# OSP_Carrier_V8_Power.net
KiCad netlist of a schematic drawn in Altium Designer
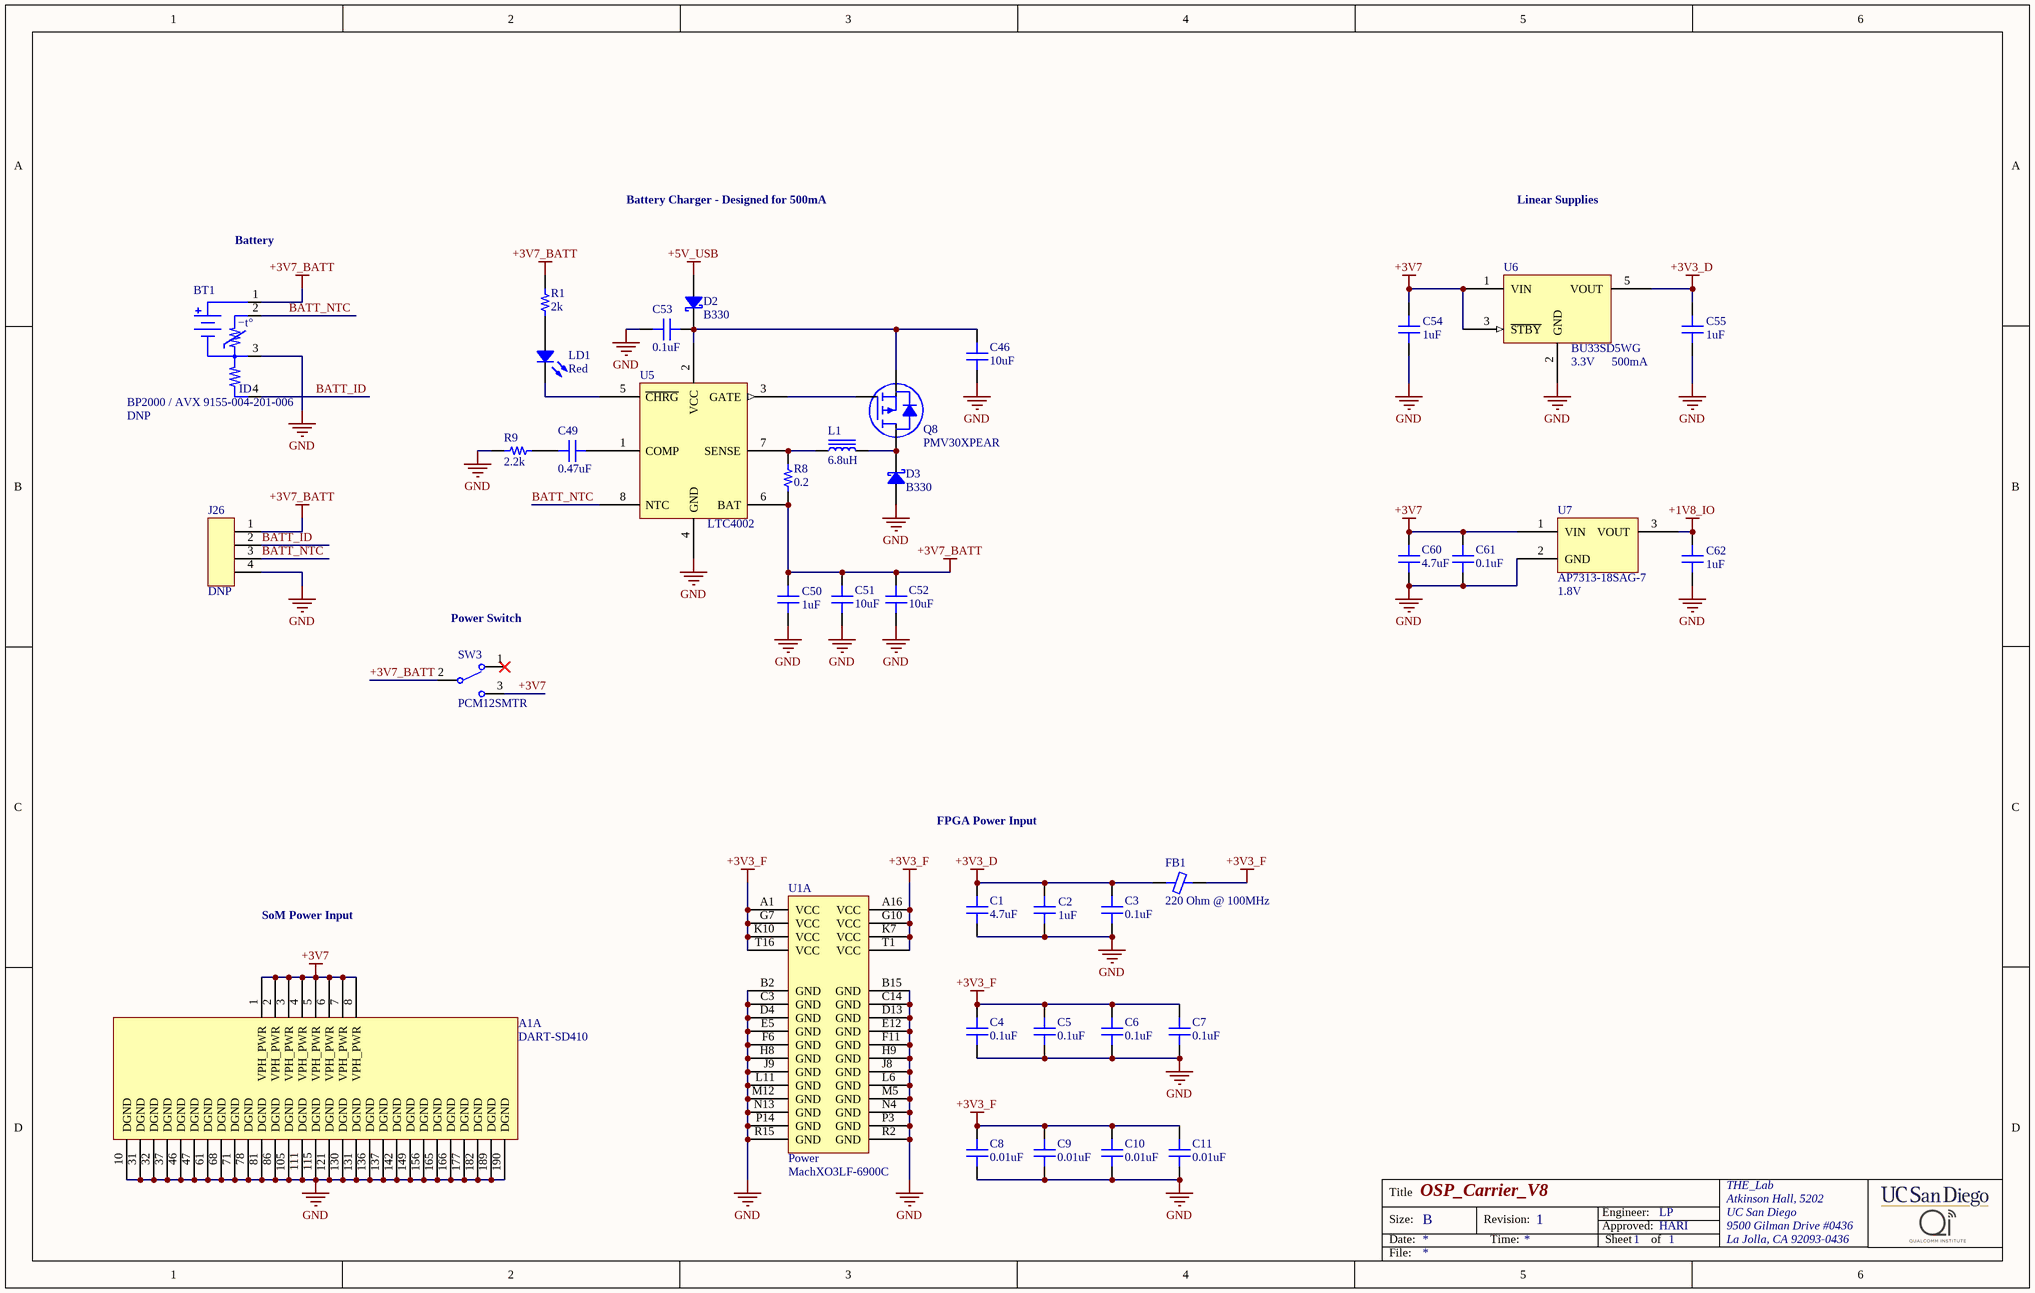
[diagram p0: OSP_Carrier_V8_Power.SchDoc]

(export (version "E")
  (design (tool "Eeschema 10.0.6"))
  (components
    (comp (ref "A1")
      (value "DART-SD410")
      (footprint "DART-SD410")
      (description "Variscite DART-SD410 System on Module")
      (libsource (lib "DART-SD410") (part "DART-SD410"))
    )
    (comp (ref "BT1")
      (value "BP2000 / AVX 9155-004-201-006")
      (footprint "SAMSUNG_BP2000")
      (description "Samsung BP2000 2000mAh battery for Galaxy Camera 2, connector AVX 9155-004-201-006")
      (fields (field (name "DNP") "DNP"))
      (libsource (lib "OSP_Symbols") (part "SAMSUNG_BP2000"))
    )
    (comp (ref "C1")
      (value "4.7uF")
      (footprint "CAP 0402/1005")
      (description "CAP CER 4.7UF 10V X5R 0402")
      (fields
        (field (name "PART NUMBER") "C1005X5R1A475K050BC")
        (field (name "MANUFACTURER") "TDK Corporation")
      )
      (libsource (lib "Celestial Library Database") (part "Capacitor"))
    )
    (comp (ref "C2")
      (value "1uF")
      (footprint "CAP 0402/1005")
      (description "CAP CER 1UF 10V X5R 0402")
      (fields
        (field (name "PART NUMBER") "GRM155R61A105KE15D")
        (field (name "MANUFACTURER") "Murata Electronics North America")
      )
      (libsource (lib "Celestial Library Database") (part "Capacitor"))
    )
    (comp (ref "C3")
      (value "0.1uF")
      (footprint "CAP 0402/1005")
      (description "CAP CER 0.1UF 50V X7R 0402")
      (fields
        (field (name "PART NUMBER") "C1005X7R1H104K050BB")
        (field (name "MANUFACTURER") "TDK Corporation")
      )
      (libsource (lib "Celestial Library Database") (part "Capacitor"))
    )
    (comp (ref "C4")
      (value "0.1uF")
      (footprint "CAP 0402/1005")
      (description "CAP CER 0.1UF 50V X7R 0402")
      (fields
        (field (name "PART NUMBER") "C1005X7R1H104K050BB")
        (field (name "MANUFACTURER") "TDK Corporation")
      )
      (libsource (lib "Celestial Library Database") (part "Capacitor"))
    )
    (comp (ref "C5")
      (value "0.1uF")
      (footprint "CAP 0402/1005")
      (description "CAP CER 0.1UF 50V X7R 0402")
      (fields
        (field (name "PART NUMBER") "C1005X7R1H104K050BB")
        (field (name "MANUFACTURER") "TDK Corporation")
      )
      (libsource (lib "Celestial Library Database") (part "Capacitor"))
    )
    (comp (ref "C6")
      (value "0.1uF")
      (footprint "CAP 0402/1005")
      (description "CAP CER 0.1UF 50V X7R 0402")
      (fields
        (field (name "PART NUMBER") "C1005X7R1H104K050BB")
        (field (name "MANUFACTURER") "TDK Corporation")
      )
      (libsource (lib "Celestial Library Database") (part "Capacitor"))
    )
    (comp (ref "C7")
      (value "0.1uF")
      (footprint "CAP 0402/1005")
      (description "CAP CER 0.1UF 50V X7R 0402")
      (fields
        (field (name "PART NUMBER") "C1005X7R1H104K050BB")
        (field (name "MANUFACTURER") "TDK Corporation")
      )
      (libsource (lib "Celestial Library Database") (part "Capacitor"))
    )
    (comp (ref "C8")
      (value "0.01uF")
      (footprint "CAP 0402/1005")
      (description "CAP CER 10000PF 25V X7R 0402")
      (fields (field (name "PART NUMBER") "CC0402KRX7R8BB103") (field (name "MANUFACTURER") "Yageo"))
      (libsource (lib "Celestial Library Database") (part "Capacitor"))
    )
    (comp (ref "C9")
      (value "0.01uF")
      (footprint "CAP 0402/1005")
      (description "CAP CER 10000PF 25V X7R 0402")
      (fields (field (name "PART NUMBER") "CC0402KRX7R8BB103") (field (name "MANUFACTURER") "Yageo"))
      (libsource (lib "Celestial Library Database") (part "Capacitor"))
    )
    (comp (ref "C10")
      (value "0.01uF")
      (footprint "CAP 0402/1005")
      (description "CAP CER 10000PF 25V X7R 0402")
      (fields (field (name "PART NUMBER") "CC0402KRX7R8BB103") (field (name "MANUFACTURER") "Yageo"))
      (libsource (lib "Celestial Library Database") (part "Capacitor"))
    )
    (comp (ref "C11")
      (value "0.01uF")
      (footprint "CAP 0402/1005")
      (description "CAP CER 10000PF 25V X7R 0402")
      (fields (field (name "PART NUMBER") "CC0402KRX7R8BB103") (field (name "MANUFACTURER") "Yageo"))
      (libsource (lib "Celestial Library Database") (part "Capacitor"))
    )
    (comp (ref "C46")
      (value "10uF")
      (footprint "CAP 1206/3216")
      (description "CAP CER 10UF 25V X7R 1206")
      (fields (field (name "PART NUMBER") "C1206C106M3RACTU") (field (name "MANUFACTURER") "Kemet"))
      (libsource (lib "Celestial Library Database") (part "Capacitor"))
    )
    (comp (ref "C49")
      (value "0.47uF")
      (footprint "CAP 0402/1005")
      (description "CAP CER 0.47UF 10V X5R 0402")
      (fields
        (field (name "PART NUMBER") "GRM155R61A474KE15D")
        (field (name "MANUFACTURER") "Murata Electronics North America")
      )
      (libsource (lib "Celestial Library Database") (part "Capacitor"))
    )
    (comp (ref "C50")
      (value "1uF")
      (footprint "CAP 0402/1005")
      (description "CAP CER 1UF 10V X5R 0402")
      (fields
        (field (name "PART NUMBER") "GRM155R61A105KE15D")
        (field (name "MANUFACTURER") "Murata Electronics North America")
      )
      (libsource (lib "Celestial Library Database") (part "Capacitor"))
    )
    (comp (ref "C51")
      (value "10uF")
      (footprint "CAP 1206/3216")
      (description "CAP CER 10UF 25V X7R 1206")
      (fields (field (name "PART NUMBER") "C1206C106M3RACTU") (field (name "MANUFACTURER") "Kemet"))
      (libsource (lib "Celestial Library Database") (part "Capacitor"))
    )
    (comp (ref "C52")
      (value "10uF")
      (footprint "CAP 1206/3216")
      (description "CAP CER 10UF 25V X7R 1206")
      (fields (field (name "PART NUMBER") "C1206C106M3RACTU") (field (name "MANUFACTURER") "Kemet"))
      (libsource (lib "Celestial Library Database") (part "Capacitor"))
    )
    (comp (ref "C53")
      (value "0.1uF")
      (footprint "CAP 0402/1005")
      (description "CAP CER 0.1UF 50V X7R 0402")
      (fields
        (field (name "PART NUMBER") "C1005X7R1H104K050BB")
        (field (name "MANUFACTURER") "TDK Corporation")
      )
      (libsource (lib "Celestial Library Database") (part "Capacitor"))
    )
    (comp (ref "C54")
      (value "1uF")
      (footprint "CAP 0402/1005")
      (description "CAP CER 1UF 10V X5R 0402")
      (fields
        (field (name "PART NUMBER") "GRM155R61A105KE15D")
        (field (name "MANUFACTURER") "Murata Electronics North America")
      )
      (libsource (lib "Celestial Library Database") (part "Capacitor"))
    )
    (comp (ref "C55")
      (value "1uF")
      (footprint "CAP 0402/1005")
      (description "CAP CER 1UF 10V X5R 0402")
      (fields
        (field (name "PART NUMBER") "GRM155R61A105KE15D")
        (field (name "MANUFACTURER") "Murata Electronics North America")
      )
      (libsource (lib "Celestial Library Database") (part "Capacitor"))
    )
    (comp (ref "C60")
      (value "4.7uF")
      (footprint "CAP 0402/1005")
      (description "CAP CER 4.7UF 10V X5R 0402")
      (fields
        (field (name "PART NUMBER") "C1005X5R1A475K050BC")
        (field (name "MANUFACTURER") "TDK Corporation")
      )
      (libsource (lib "Celestial Library Database") (part "Capacitor"))
    )
    (comp (ref "C61")
      (value "0.1uF")
      (footprint "CAP 0402/1005")
      (description "CAP CER 0.1UF 50V X7R 0402")
      (fields
        (field (name "PART NUMBER") "C1005X7R1H104K050BB")
        (field (name "MANUFACTURER") "TDK Corporation")
      )
      (libsource (lib "Celestial Library Database") (part "Capacitor"))
    )
    (comp (ref "C62")
      (value "1uF")
      (footprint "CAP 0402/1005")
      (description "CAP CER 1UF 10V X5R 0402")
      (fields
        (field (name "PART NUMBER") "GRM155R61A105KE15D")
        (field (name "MANUFACTURER") "Murata Electronics North America")
      )
      (libsource (lib "Celestial Library Database") (part "Capacitor"))
    )
    (comp (ref "D2")
      (value "B330")
      (footprint "DO214AC SMA")
      (description "B330AE-13 Schottky Diode 3A 30V")
      (libsource (lib "OSP_Symbols") (part "B330A"))
    )
    (comp (ref "D3")
      (value "B330")
      (footprint "DO214AC SMA")
      (description "B330AE-13 Schottky Diode 3A 30V")
      (libsource (lib "OSP_Symbols") (part "B330A"))
    )
    (comp (ref "FB1")
      (value "220 Ohm @ 100MHz")
      (footprint "FER 0402/1005")
      (description "FERRITE CHIP 220 OHM 500MA 0402")
      (fields
        (field (name "PART NUMBER") "CIM05U221NC")
        (field (name "MANUFACTURER") "Samsung Electro-Mechanics America, Inc.")
      )
      (libsource (lib "Celestial Library Database") (part "Ferrite Chip"))
    )
    (comp (ref "J26")
      (value "Shallow")
      (footprint "AMPHENOL_10125839-04RAEHLF_DNP")
      (description "Amphenol 10125839-04RAEHLF (Do Not Populate)")
      (fields (field (name "DNP") "DNP"))
      (libsource (lib "OSP_Symbols") (part "AMPHENOL_10125839-04RAEHLF_DNP"))
    )
    (comp (ref "L1")
      (value "6.8uH")
      (footprint "LAIRD_TYS6028")
      (description "Laird TYS60286R8M-10 6.8uH 2.4A 47mOhms")
      (libsource (lib "OSP_Symbols") (part "Laird_TYS60286R8M-10"))
    )
    (comp (ref "LD1")
      (value "Red")
      (footprint "LED 0603/1608 RED")
      (description "LED RED CLEAR 0603 SMD")
      (fields (field (name "PART NUMBER") "LTST-C191KRKT") (field (name "MANUFACTURER") "Lite-On Inc."))
      (libsource (lib "Celestial Library Database") (part "LED"))
    )
    (comp (ref "Q8")
      (value "PMV30XPEAR")
      (footprint "NXP_SOT23")
      (description "PMV30XPEAR PMOS 20V -5.3A 28mOhms")
      (libsource (lib "OSP_Symbols") (part "NXP_PMV30XPEAR"))
    )
    (comp (ref "R1")
      (value "2k")
      (footprint "RES 0402/1005")
      (description "RES SMD 2K OHM 1% 1/10W 0402")
      (fields
        (field (name "PART NUMBER") "ERJ-2RKF2001X")
        (field (name "MANUFACTURER") "Panasonic Electronic Components")
      )
      (libsource (lib "Celestial Library Database") (part "Resistor"))
    )
    (comp (ref "R8")
      (value "0.2")
      (footprint "STACKPOLE CSR1206")
      (description "RES SMD 0.2 OHM 1% 1/2W 1206")
      (fields
        (field (name "PART NUMBER") "CSR1206FKR200")
        (field (name "MANUFACTURER") "Stackpole Electronics Inc.")
      )
      (libsource (lib "Celestial Library Database") (part "Resistor"))
    )
    (comp (ref "R9")
      (value "2.2k")
      (footprint "RES 0402/1005")
      (description "RES SMD 2.2K OHM 1% 1/10W 0402")
      (fields
        (field (name "PART NUMBER") "ERJ-2RKF2201X")
        (field (name "MANUFACTURER") "Panasonic Electronic Components")
      )
      (libsource (lib "Celestial Library Database") (part "Resistor"))
    )
    (comp (ref "SW3")
      (value "PCM12SMTR")
      (footprint "*SW_PCM12SMTR_PCM12SMTR(Primary)")
      (libsource (lib "PCM12SMTR") (part "PCM12SMTR"))
    )
    (comp (ref "U1")
      (value "MachXO3LF-6900C")
      (footprint "LCMXO3_caBGA_BG256")
      (description "Lattice MachXO3LF-6900C-5BG256C FPGA")
      (libsource (lib "OSP_Symbols") (part "LCMXO3LF-6900C-XBG256X"))
    )
    (comp (ref "U5")
      (value "LTC4002")
      (footprint "AD_LT_S8")
      (description "Analog / Linear 1.5A Single Cell Li-Ion Battery Charger")
      (libsource (lib "OSP_Symbols") (part "LTC4002"))
    )
    (comp (ref "U6")
      (value "BU33SD5WG")
      (footprint "ROHM_SSOP5")
      (description "ROHM BU33SD5WG-TR 3.3V 500mA LDO")
      (fields (field (name "VOLTAGE") "3.3V") (field (name "CURRENT") "500mA"))
      (libsource (lib "OSP_Symbols") (part "ROHM_BU33SD5WG"))
    )
    (comp (ref "U7")
      (value "AP7313-18SAG-7")
      (footprint "DIODES SOT-23-3")
      (description "IC REG LDO 1.8V 0.15A SOT23-3")
      (fields (field (name "MANUFACTURER") "Diodes Incorporated") (field (name "VOLTAGE - OUTPUT") "1.8V"))
      (libsource (lib "Celestial Library Database") (part "Diodes Inc AP7313"))
    )
  )
  (nets
    (net (code "1") (name "+1V8_IO") (class "Default")
      (node (ref "C62") (pin "1") (pinfunction "1_1") (pintype "passive"))
      (node (ref "U7") (pin "3") (pinfunction "VOUT_3") (pintype "passive"))
    )
    (net (code "2") (name "+3V3_D") (class "Default")
      (node (ref "C1") (pin "2") (pinfunction "2_2") (pintype "passive"))
      (node (ref "C2") (pin "1") (pinfunction "1_1") (pintype "passive"))
      (node (ref "C3") (pin "2") (pinfunction "2_2") (pintype "passive"))
      (node (ref "C55") (pin "1") (pinfunction "1_1") (pintype "passive"))
      (node (ref "FB1") (pin "1") (pinfunction "1_1") (pintype "passive"))
      (node (ref "U6") (pin "5") (pinfunction "VOUT_5") (pintype "power_in"))
    )
    (net (code "3") (name "+3V3_F") (class "Default")
      (node (ref "C10") (pin "2") (pinfunction "2_2") (pintype "passive"))
      (node (ref "C11") (pin "2") (pinfunction "2_2") (pintype "passive"))
      (node (ref "C4") (pin "2") (pinfunction "2_2") (pintype "passive"))
      (node (ref "C5") (pin "2") (pinfunction "2_2") (pintype "passive"))
      (node (ref "C6") (pin "2") (pinfunction "2_2") (pintype "passive"))
      (node (ref "C7") (pin "2") (pinfunction "2_2") (pintype "passive"))
      (node (ref "C8") (pin "2") (pinfunction "2_2") (pintype "passive"))
      (node (ref "C9") (pin "2") (pinfunction "2_2") (pintype "passive"))
      (node (ref "FB1") (pin "2") (pinfunction "2_2") (pintype "passive"))
      (node (ref "U1") (pin "A1") (pinfunction "VCC_A1") (pintype "power_in"))
      (node (ref "U1") (pin "A16") (pinfunction "VCC_A16") (pintype "power_in"))
      (node (ref "U1") (pin "G10") (pinfunction "VCC_G10") (pintype "power_in"))
      (node (ref "U1") (pin "G7") (pinfunction "VCC_G7") (pintype "power_in"))
      (node (ref "U1") (pin "K10") (pinfunction "VCC_K10") (pintype "power_in"))
      (node (ref "U1") (pin "K7") (pinfunction "VCC_K7") (pintype "power_in"))
      (node (ref "U1") (pin "T1") (pinfunction "VCC_T1") (pintype "power_in"))
      (node (ref "U1") (pin "T16") (pinfunction "VCC_T16") (pintype "power_in"))
    )
    (net (code "4") (name "+3V7") (class "Default")
      (node (ref "A1") (pin "1") (pinfunction "VPH_PWR_1") (pintype "power_in"))
      (node (ref "A1") (pin "2") (pinfunction "VPH_PWR_2") (pintype "power_in"))
      (node (ref "A1") (pin "3") (pinfunction "VPH_PWR_3") (pintype "power_in"))
      (node (ref "A1") (pin "4") (pinfunction "VPH_PWR_4") (pintype "power_in"))
      (node (ref "A1") (pin "5") (pinfunction "VPH_PWR_5") (pintype "power_in"))
      (node (ref "A1") (pin "6") (pinfunction "VPH_PWR_6") (pintype "power_in"))
      (node (ref "A1") (pin "7") (pinfunction "VPH_PWR_7") (pintype "power_in"))
      (node (ref "A1") (pin "8") (pinfunction "VPH_PWR_8") (pintype "power_in"))
      (node (ref "C54") (pin "1") (pinfunction "1_1") (pintype "passive"))
      (node (ref "C60") (pin "2") (pinfunction "2_2") (pintype "passive"))
      (node (ref "C61") (pin "2") (pinfunction "2_2") (pintype "passive"))
      (node (ref "SW3") (pin "3") (pinfunction "3_3") (pintype "passive"))
      (node (ref "U6") (pin "1") (pinfunction "VIN_1") (pintype "power_in"))
      (node (ref "U6") (pin "3") (pinfunction "~{STBY}_3") (pintype "input"))
      (node (ref "U7") (pin "1") (pinfunction "VIN_1") (pintype "passive"))
    )
    (net (code "5") (name "+3V7_BATT") (class "Default")
      (node (ref "BT1") (pin "1") (pinfunction "+_1") (pintype "power_in"))
      (node (ref "C50") (pin "1") (pinfunction "1_1") (pintype "passive"))
      (node (ref "C51") (pin "1") (pinfunction "1_1") (pintype "passive"))
      (node (ref "C52") (pin "1") (pinfunction "1_1") (pintype "passive"))
      (node (ref "J26") (pin "1") (pintype "passive"))
      (node (ref "R1") (pin "2") (pinfunction "2_2") (pintype "passive"))
      (node (ref "R8") (pin "1") (pinfunction "1_1") (pintype "passive"))
      (node (ref "SW3") (pin "2") (pinfunction "2_2") (pintype "passive"))
      (node (ref "U5") (pin "6") (pinfunction "BAT_6") (pintype "passive"))
    )
    (net (code "6") (name "+5V_USB") (class "Default")
      (node (ref "D2") (pin "1") (pinfunction "1_1") (pintype "passive"))
    )
    (net (code "7") (name "/BATT_ID") (class "Default")
      (node (ref "BT1") (pin "4") (pinfunction "ID_4") (pintype "passive"))
      (node (ref "J26") (pin "2") (pintype "passive"))
    )
    (net (code "8") (name "/BATT_NTC") (class "Default")
      (node (ref "BT1") (pin "2") (pinfunction "NTC_2") (pintype "passive"))
      (node (ref "J26") (pin "3") (pintype "passive"))
      (node (ref "U5") (pin "8") (pinfunction "NTC_8") (pintype "passive"))
    )
    (net (code "9") (name "GND") (class "Default")
      (node (ref "A1") (pin "10") (pinfunction "DGND_10") (pintype "power_in"))
      (node (ref "A1") (pin "105") (pinfunction "DGND_105") (pintype "power_in"))
      (node (ref "A1") (pin "111") (pinfunction "DGND_111") (pintype "power_in"))
      (node (ref "A1") (pin "115") (pinfunction "DGND_115") (pintype "power_in"))
      (node (ref "A1") (pin "121") (pinfunction "DGND_121") (pintype "power_in"))
      (node (ref "A1") (pin "130") (pinfunction "DGND_130") (pintype "power_in"))
      (node (ref "A1") (pin "131") (pinfunction "DGND_131") (pintype "power_in"))
      (node (ref "A1") (pin "136") (pinfunction "DGND_136") (pintype "power_in"))
      (node (ref "A1") (pin "137") (pinfunction "DGND_137") (pintype "power_in"))
      (node (ref "A1") (pin "142") (pinfunction "DGND_142") (pintype "power_in"))
      (node (ref "A1") (pin "149") (pinfunction "DGND_149") (pintype "power_in"))
      (node (ref "A1") (pin "156") (pinfunction "DGND_156") (pintype "power_in"))
      (node (ref "A1") (pin "165") (pinfunction "DGND_165") (pintype "power_in"))
      (node (ref "A1") (pin "166") (pinfunction "DGND_166") (pintype "power_in"))
      (node (ref "A1") (pin "177") (pinfunction "DGND_177") (pintype "power_in"))
      (node (ref "A1") (pin "182") (pinfunction "DGND_182") (pintype "power_in"))
      (node (ref "A1") (pin "189") (pinfunction "DGND_189") (pintype "power_in"))
      (node (ref "A1") (pin "190") (pinfunction "DGND_190") (pintype "power_in"))
      (node (ref "A1") (pin "31") (pinfunction "DGND_31") (pintype "power_in"))
      (node (ref "A1") (pin "32") (pinfunction "DGND_32") (pintype "power_in"))
      (node (ref "A1") (pin "37") (pinfunction "DGND_37") (pintype "power_in"))
      (node (ref "A1") (pin "46") (pinfunction "DGND_46") (pintype "power_in"))
      (node (ref "A1") (pin "47") (pinfunction "DGND_47") (pintype "power_in"))
      (node (ref "A1") (pin "61") (pinfunction "DGND_61") (pintype "power_in"))
      (node (ref "A1") (pin "68") (pinfunction "DGND_68") (pintype "power_in"))
      (node (ref "A1") (pin "71") (pinfunction "DGND_71") (pintype "power_in"))
      (node (ref "A1") (pin "78") (pinfunction "DGND_78") (pintype "power_in"))
      (node (ref "A1") (pin "81") (pinfunction "DGND_81") (pintype "power_in"))
      (node (ref "A1") (pin "86") (pinfunction "DGND_86") (pintype "power_in"))
      (node (ref "BT1") (pin "3") (pinfunction "−_3") (pintype "power_in"))
      (node (ref "C1") (pin "1") (pinfunction "1_1") (pintype "passive"))
      (node (ref "C10") (pin "1") (pinfunction "1_1") (pintype "passive"))
      (node (ref "C11") (pin "1") (pinfunction "1_1") (pintype "passive"))
      (node (ref "C2") (pin "2") (pinfunction "2_2") (pintype "passive"))
      (node (ref "C3") (pin "1") (pinfunction "1_1") (pintype "passive"))
      (node (ref "C4") (pin "1") (pinfunction "1_1") (pintype "passive"))
      (node (ref "C46") (pin "2") (pinfunction "2_2") (pintype "passive"))
      (node (ref "C5") (pin "1") (pinfunction "1_1") (pintype "passive"))
      (node (ref "C50") (pin "2") (pinfunction "2_2") (pintype "passive"))
      (node (ref "C51") (pin "2") (pinfunction "2_2") (pintype "passive"))
      (node (ref "C52") (pin "2") (pinfunction "2_2") (pintype "passive"))
      (node (ref "C53") (pin "2") (pinfunction "2_2") (pintype "passive"))
      (node (ref "C54") (pin "2") (pinfunction "2_2") (pintype "passive"))
      (node (ref "C55") (pin "2") (pinfunction "2_2") (pintype "passive"))
      (node (ref "C6") (pin "1") (pinfunction "1_1") (pintype "passive"))
      (node (ref "C60") (pin "1") (pinfunction "1_1") (pintype "passive"))
      (node (ref "C61") (pin "1") (pinfunction "1_1") (pintype "passive"))
      (node (ref "C62") (pin "2") (pinfunction "2_2") (pintype "passive"))
      (node (ref "C7") (pin "1") (pinfunction "1_1") (pintype "passive"))
      (node (ref "C8") (pin "1") (pinfunction "1_1") (pintype "passive"))
      (node (ref "C9") (pin "1") (pinfunction "1_1") (pintype "passive"))
      (node (ref "D3") (pin "1") (pinfunction "1_1") (pintype "passive"))
      (node (ref "J26") (pin "4") (pintype "passive"))
      (node (ref "R9") (pin "2") (pinfunction "2_2") (pintype "passive"))
      (node (ref "U1") (pin "B15") (pinfunction "GND_B15") (pintype "power_in"))
      (node (ref "U1") (pin "B2") (pinfunction "GND_B2") (pintype "power_in"))
      (node (ref "U1") (pin "C14") (pinfunction "GND_C14") (pintype "power_in"))
      (node (ref "U1") (pin "C3") (pinfunction "GND_C3") (pintype "power_in"))
      (node (ref "U1") (pin "D13") (pinfunction "GND_D13") (pintype "power_in"))
      (node (ref "U1") (pin "D4") (pinfunction "GND_D4") (pintype "power_in"))
      (node (ref "U1") (pin "E12") (pinfunction "GND_E12") (pintype "power_in"))
      (node (ref "U1") (pin "E5") (pinfunction "GND_E5") (pintype "power_in"))
      (node (ref "U1") (pin "F11") (pinfunction "GND_F11") (pintype "power_in"))
      (node (ref "U1") (pin "F6") (pinfunction "GND_F6") (pintype "power_in"))
      (node (ref "U1") (pin "H8") (pinfunction "GND_H8") (pintype "power_in"))
      (node (ref "U1") (pin "H9") (pinfunction "GND_H9") (pintype "power_in"))
      (node (ref "U1") (pin "J8") (pinfunction "GND_J8") (pintype "power_in"))
      (node (ref "U1") (pin "J9") (pinfunction "GND_J9") (pintype "power_in"))
      (node (ref "U1") (pin "L11") (pinfunction "GND_L11") (pintype "power_in"))
      (node (ref "U1") (pin "L6") (pinfunction "GND_L6") (pintype "power_in"))
      (node (ref "U1") (pin "M12") (pinfunction "GND_M12") (pintype "power_in"))
      (node (ref "U1") (pin "M5") (pinfunction "GND_M5") (pintype "power_in"))
      (node (ref "U1") (pin "N13") (pinfunction "GND_N13") (pintype "power_in"))
      (node (ref "U1") (pin "N4") (pinfunction "GND_N4") (pintype "power_in"))
      (node (ref "U1") (pin "P14") (pinfunction "GND_P14") (pintype "power_in"))
      (node (ref "U1") (pin "P3") (pinfunction "GND_P3") (pintype "power_in"))
      (node (ref "U1") (pin "R15") (pinfunction "GND_R15") (pintype "power_in"))
      (node (ref "U1") (pin "R2") (pinfunction "GND_R2") (pintype "power_in"))
      (node (ref "U5") (pin "4") (pinfunction "GND_4") (pintype "power_in"))
      (node (ref "U6") (pin "2") (pinfunction "GND_2") (pintype "power_in"))
      (node (ref "U7") (pin "2") (pinfunction "GND_2") (pintype "passive"))
    )
    (net (code "10") (name "Net-(C49-Pad2)") (class "Default")
      (node (ref "C49") (pin "2") (pinfunction "2_2") (pintype "passive"))
      (node (ref "R9") (pin "1") (pinfunction "1_1") (pintype "passive"))
    )
    (net (code "11") (name "Net-(LD1-Pad1)") (class "Default")
      (node (ref "LD1") (pin "1") (pinfunction "1_1") (pintype "passive"))
      (node (ref "R1") (pin "1") (pinfunction "1_1") (pintype "passive"))
    )
    (net (code "12") (name "Net-(Q8-D)") (class "Default")
      (node (ref "D3") (pin "2") (pinfunction "2_2") (pintype "passive"))
      (node (ref "L1") (pin "2") (pinfunction "2_2") (pintype "passive"))
      (node (ref "Q8") (pin "3") (pinfunction "D_3") (pintype "passive"))
    )
    (net (code "13") (name "Net-(Q8-G)") (class "Default")
      (node (ref "Q8") (pin "1") (pinfunction "G_1") (pintype "passive"))
      (node (ref "U5") (pin "3") (pinfunction "GATE_3") (pintype "output"))
    )
    (net (code "14") (name "Net-(Q8-S)") (class "Default")
      (node (ref "C46") (pin "1") (pinfunction "1_1") (pintype "passive"))
      (node (ref "C53") (pin "1") (pinfunction "1_1") (pintype "passive"))
      (node (ref "D2") (pin "2") (pinfunction "2_2") (pintype "passive"))
      (node (ref "Q8") (pin "2") (pinfunction "S_2") (pintype "passive"))
      (node (ref "U5") (pin "2") (pinfunction "VCC_2") (pintype "power_in"))
    )
    (net (code "15") (name "Net-(U5-COMP)") (class "Default")
      (node (ref "C49") (pin "1") (pinfunction "1_1") (pintype "passive"))
      (node (ref "U5") (pin "1") (pinfunction "COMP_1") (pintype "passive"))
    )
    (net (code "16") (name "Net-(U5-SENSE)") (class "Default")
      (node (ref "L1") (pin "1") (pinfunction "1_1") (pintype "passive"))
      (node (ref "R8") (pin "2") (pinfunction "2_2") (pintype "passive"))
      (node (ref "U5") (pin "7") (pinfunction "SENSE_7") (pintype "passive"))
    )
    (net (code "17") (name "Net-(U5-~{CHRG})") (class "Default")
      (node (ref "LD1") (pin "2") (pinfunction "2_2") (pintype "passive"))
      (node (ref "U5") (pin "5") (pinfunction "~{CHRG}_5") (pintype "open_collector"))
    )
    (net (code "18") (name "unconnected-(SW3-Pad1)") (class "Default")
      (node (ref "SW3") (pin "1") (pinfunction "1_1") (pintype "passive+no_connect"))
    )
  )
)
